# eMMC.net
KiCad netlist of a schematic drawn in Altium Designer
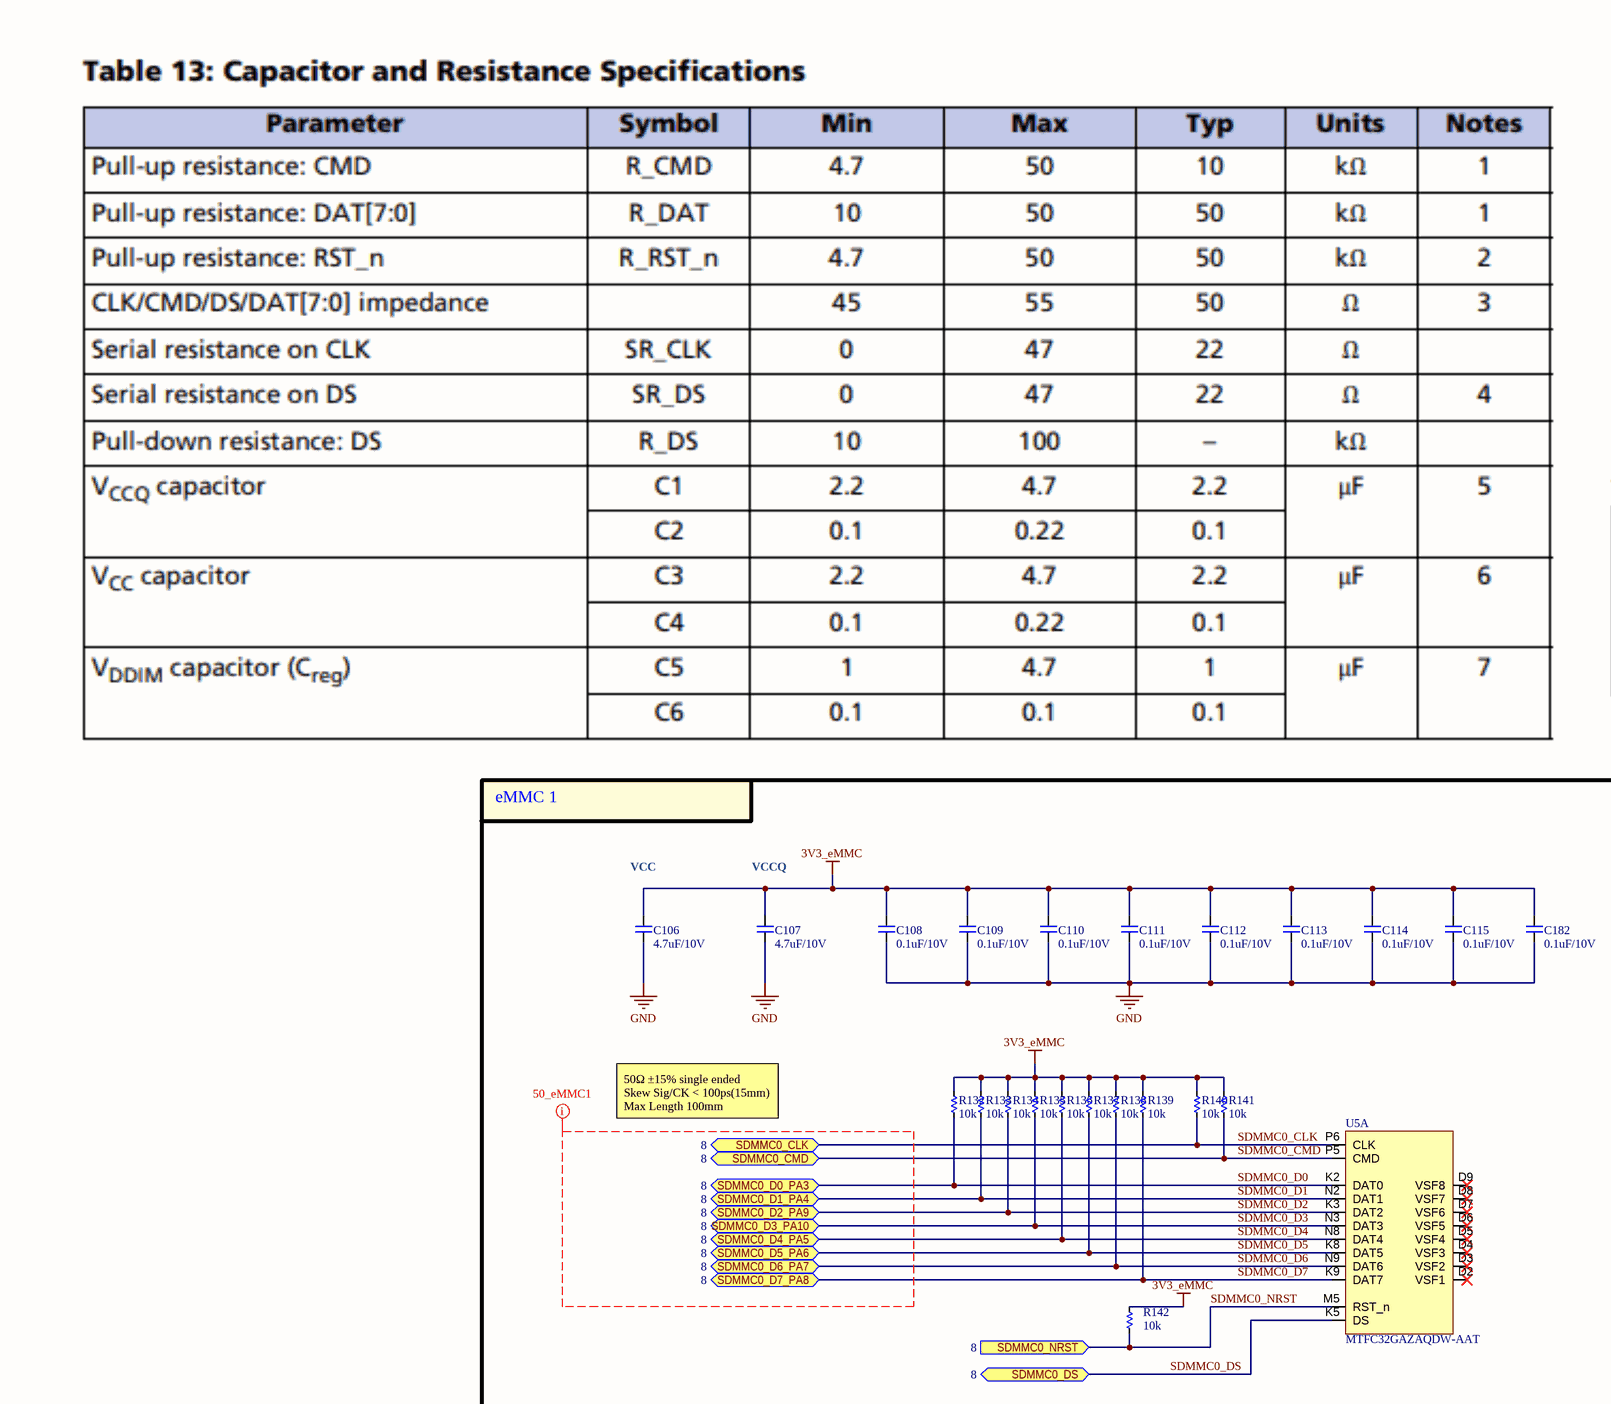
[diagram p0: eMMC.SchDoc, top left]
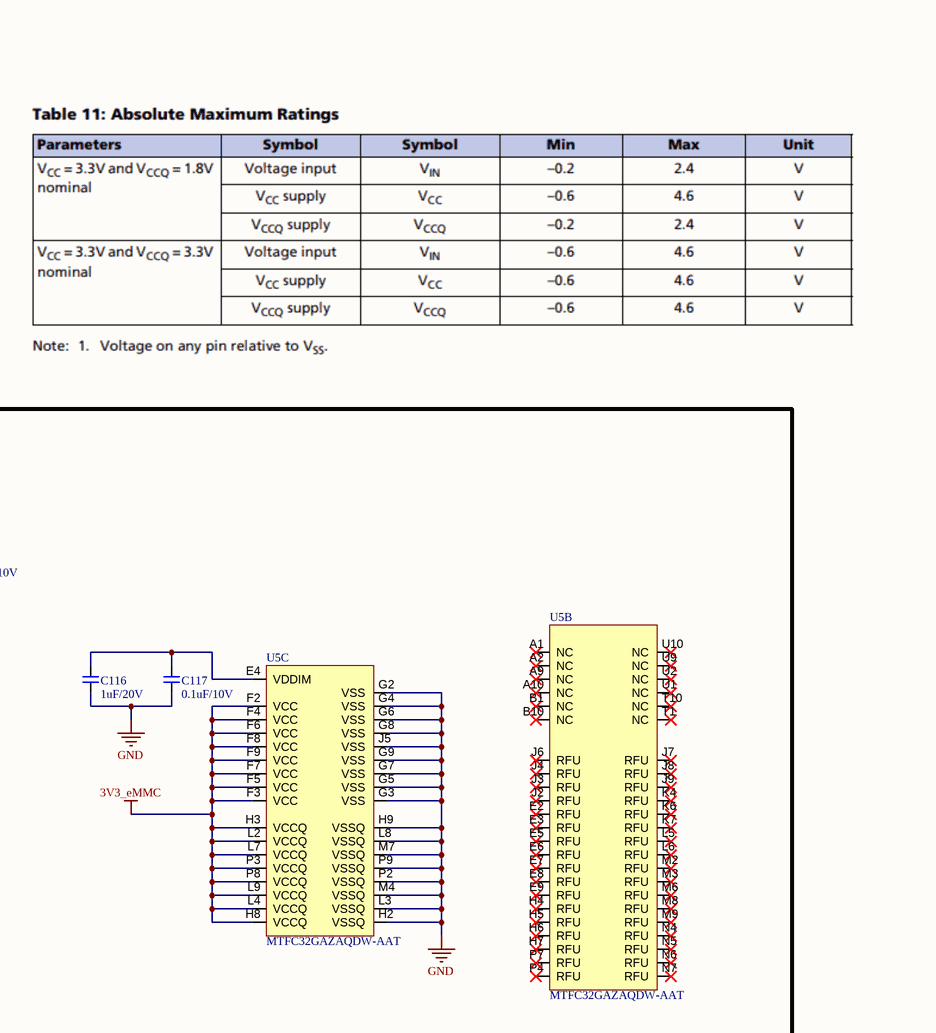
[diagram p1: eMMC.SchDoc, top middle]
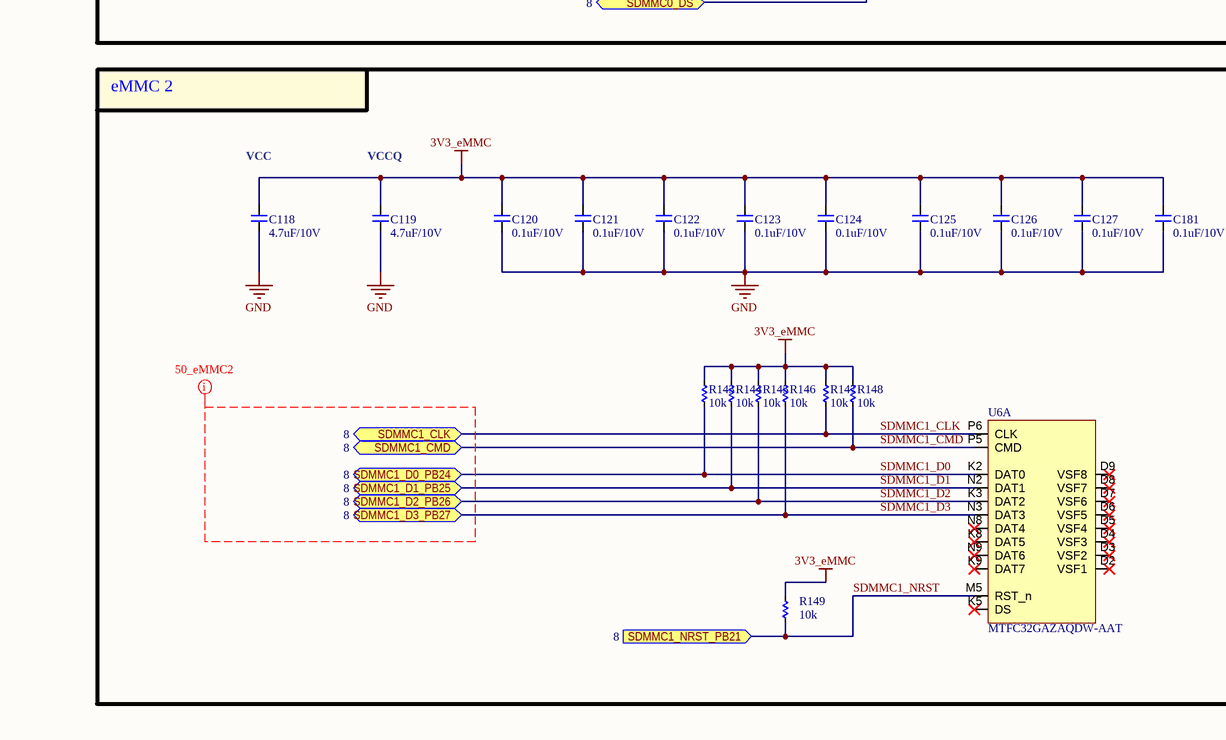
[diagram p2: eMMC.SchDoc, bottom left]
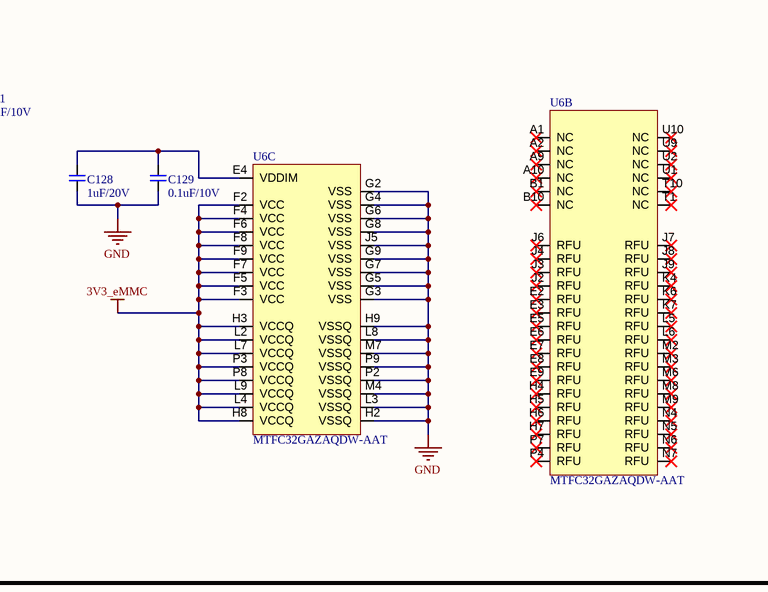
[diagram p3: eMMC.SchDoc, bottom middle]
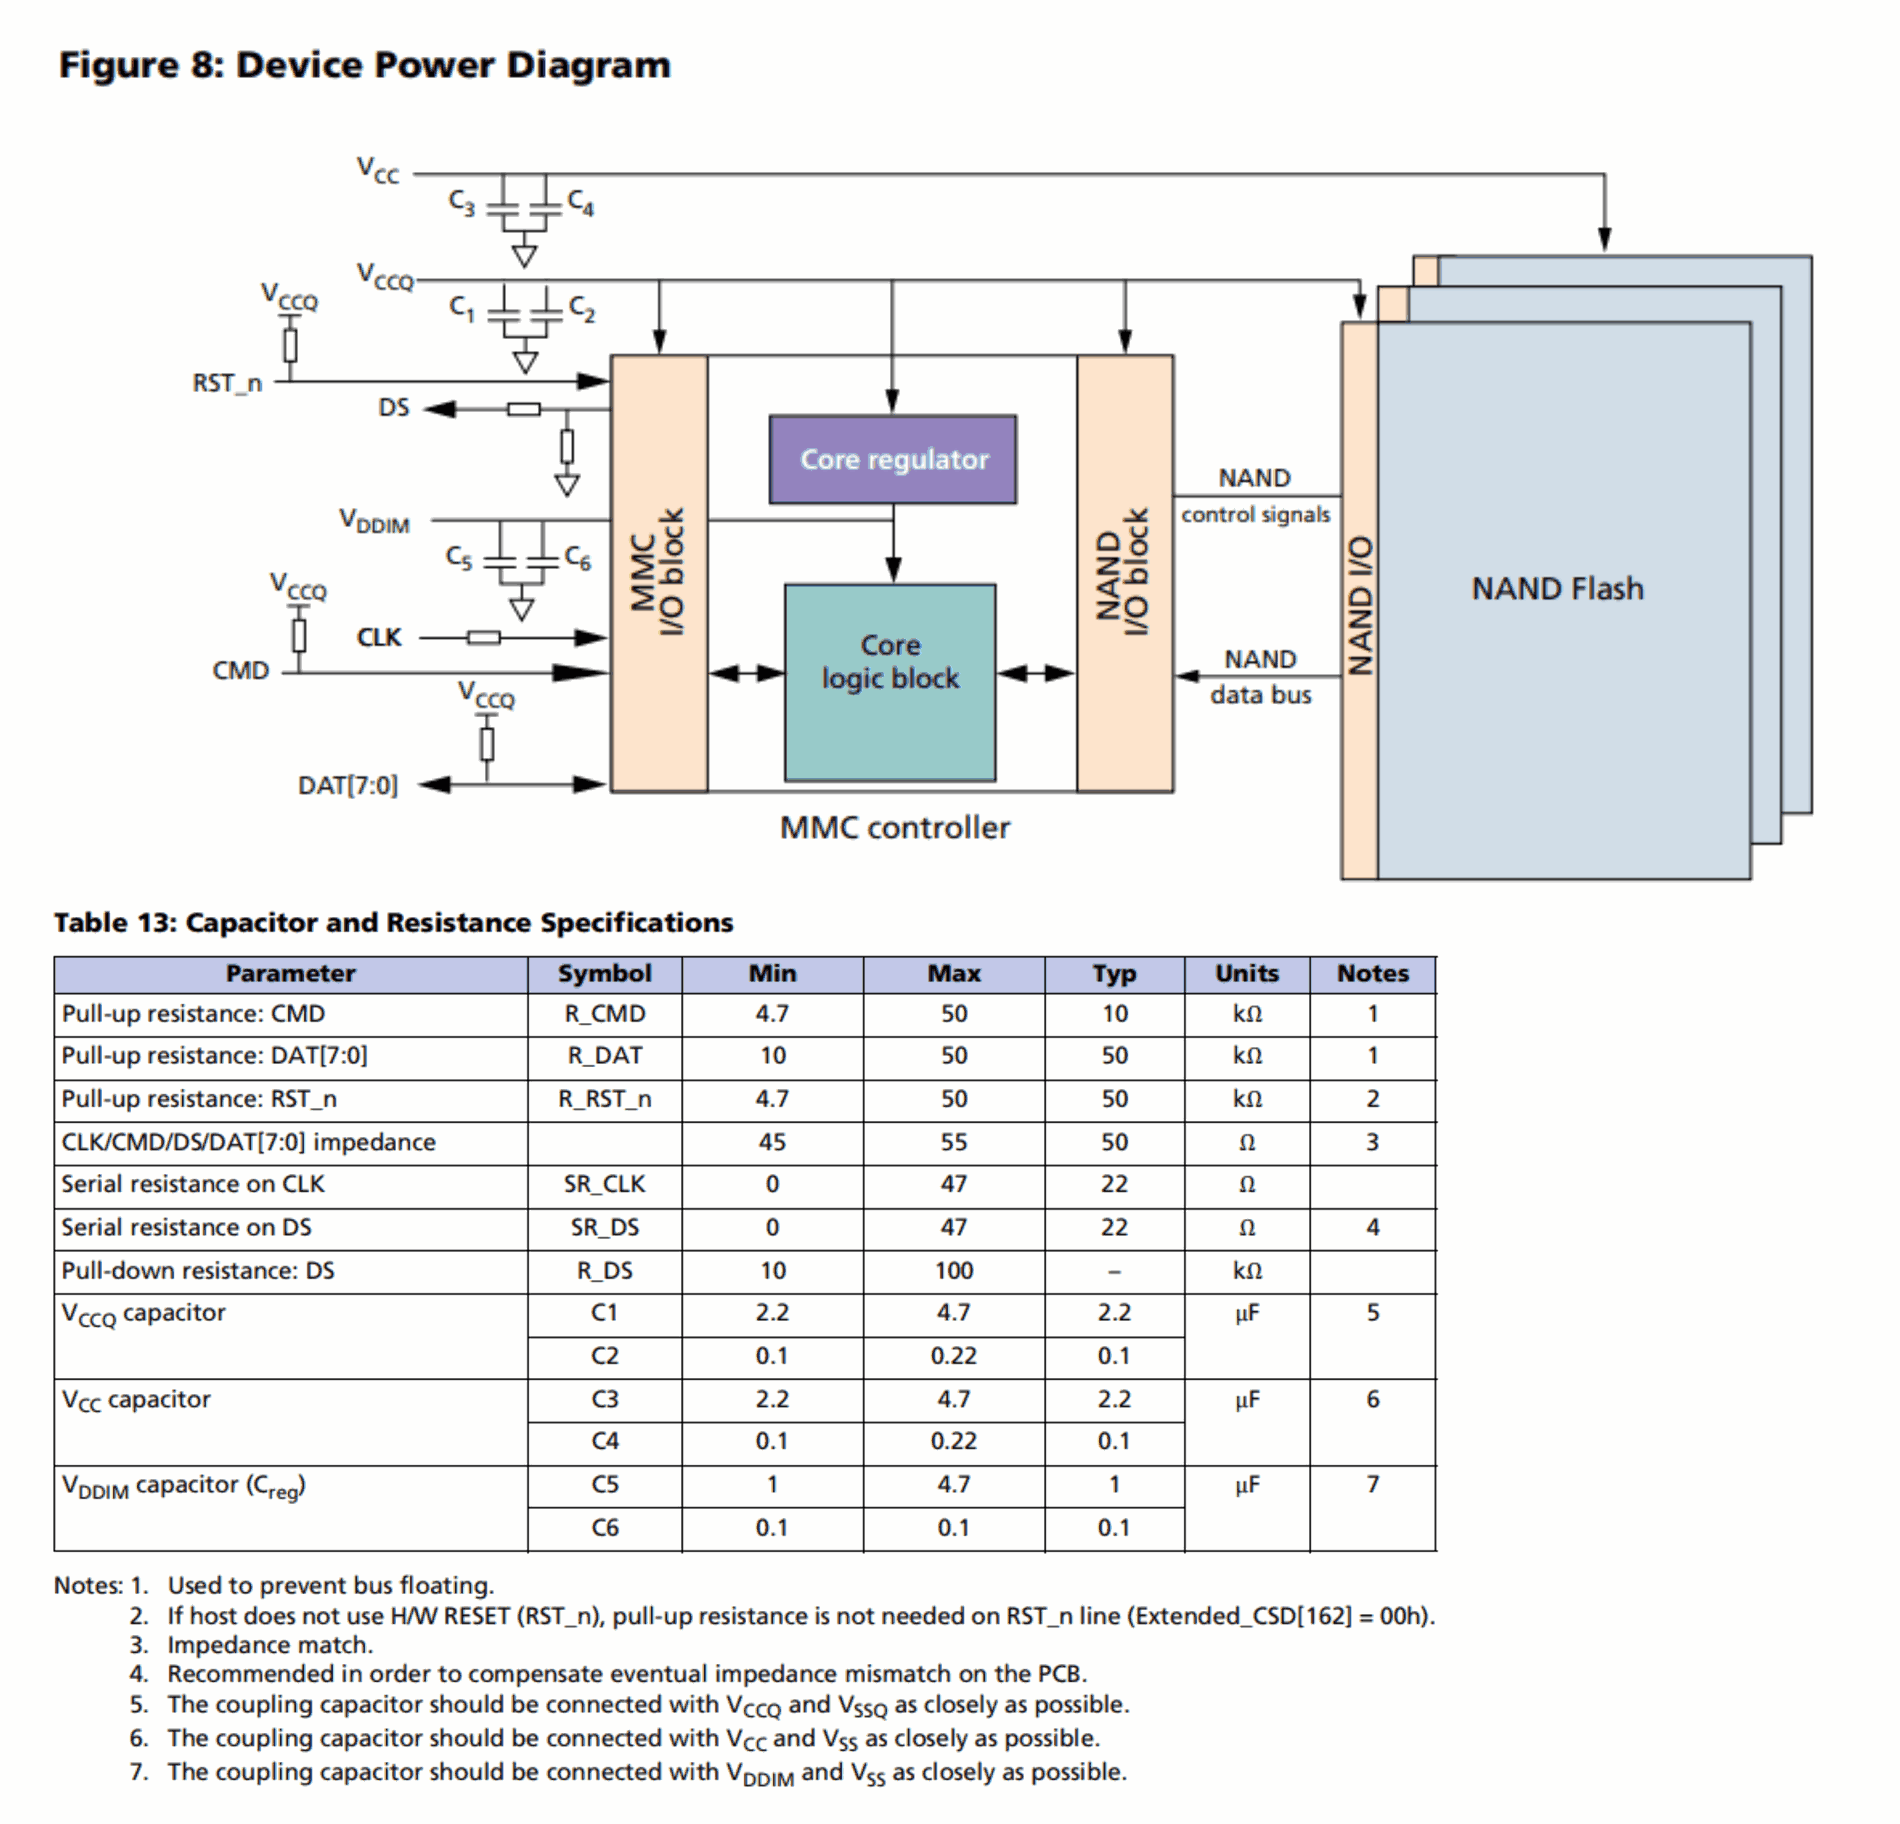
[diagram p4: eMMC.SchDoc, bottom right]

(export (version "E")
  (design (tool "Eeschema 10.0.6"))
  (components
    (comp (ref "C106")
      (value "4.7uF/10V")
      (footprint "CAP_C_1005X50_L")
      (description "CAP CHIP")
      (libsource (lib "IFBschelib") (part "_CAP_C_2"))
    )
    (comp (ref "C107")
      (value "4.7uF/10V")
      (footprint "CAP_C_1005X50_L")
      (description "CAP CHIP")
      (libsource (lib "IFBschelib") (part "_CAP_C_2"))
    )
    (comp (ref "C108")
      (value "0.1uF/10V")
      (footprint "CAP_C_1005X50_L")
      (description "CAP CHIP")
      (libsource (lib "IFBschelib") (part "_CAP_C_2"))
    )
    (comp (ref "C109")
      (value "0.1uF/10V")
      (footprint "CAP_C_1005X50_L")
      (description "CAP CHIP")
      (libsource (lib "IFBschelib") (part "_CAP_C_2"))
    )
    (comp (ref "C110")
      (value "0.1uF/10V")
      (footprint "CAP_C_1005X50_L")
      (description "CAP CHIP")
      (libsource (lib "IFBschelib") (part "_CAP_C_2"))
    )
    (comp (ref "C111")
      (value "0.1uF/10V")
      (footprint "CAP_C_1005X50_L")
      (description "CAP CHIP")
      (libsource (lib "IFBschelib") (part "_CAP_C_2"))
    )
    (comp (ref "C112")
      (value "0.1uF/10V")
      (footprint "CAP_C_1005X50_L")
      (description "CAP CHIP")
      (libsource (lib "IFBschelib") (part "_CAP_C_2"))
    )
    (comp (ref "C113")
      (value "0.1uF/10V")
      (footprint "CAP_C_1005X50_L")
      (description "CAP CHIP")
      (libsource (lib "IFBschelib") (part "_CAP_C_2"))
    )
    (comp (ref "C114")
      (value "0.1uF/10V")
      (footprint "CAP_C_1005X50_L")
      (description "CAP CHIP")
      (libsource (lib "IFBschelib") (part "_CAP_C_2"))
    )
    (comp (ref "C115")
      (value "0.1uF/10V")
      (footprint "CAP_C_1005X50_L")
      (description "CAP CHIP")
      (libsource (lib "IFBschelib") (part "_CAP_C_2"))
    )
    (comp (ref "C116")
      (value "1uF/20V")
      (footprint "CAP_C_1005X50_L")
      (description "CAP CHIP")
      (libsource (lib "IFBschelib") (part "_CAP_C_2"))
    )
    (comp (ref "C117")
      (value "0.1uF/10V")
      (footprint "CAP_C_1005X50_L")
      (description "CAP CHIP")
      (libsource (lib "IFBschelib") (part "_CAP_C_2"))
    )
    (comp (ref "C118")
      (value "4.7uF/10V")
      (footprint "CAP_C_1005X50_L")
      (description "CAP CHIP")
      (libsource (lib "IFBschelib") (part "_CAP_C_2"))
    )
    (comp (ref "C119")
      (value "4.7uF/10V")
      (footprint "CAP_C_1005X50_L")
      (description "CAP CHIP")
      (libsource (lib "IFBschelib") (part "_CAP_C_2"))
    )
    (comp (ref "C120")
      (value "0.1uF/10V")
      (footprint "CAP_C_1005X50_L")
      (description "CAP CHIP")
      (libsource (lib "IFBschelib") (part "_CAP_C_2"))
    )
    (comp (ref "C121")
      (value "0.1uF/10V")
      (footprint "CAP_C_1005X50_L")
      (description "CAP CHIP")
      (libsource (lib "IFBschelib") (part "_CAP_C_2"))
    )
    (comp (ref "C122")
      (value "0.1uF/10V")
      (footprint "CAP_C_1005X50_L")
      (description "CAP CHIP")
      (libsource (lib "IFBschelib") (part "_CAP_C_2"))
    )
    (comp (ref "C123")
      (value "0.1uF/10V")
      (footprint "CAP_C_1005X50_L")
      (description "CAP CHIP")
      (libsource (lib "IFBschelib") (part "_CAP_C_2"))
    )
    (comp (ref "C124")
      (value "0.1uF/10V")
      (footprint "CAP_C_1005X50_L")
      (description "CAP CHIP")
      (libsource (lib "IFBschelib") (part "_CAP_C_2"))
    )
    (comp (ref "C125")
      (value "0.1uF/10V")
      (footprint "CAP_C_1005X50_L")
      (description "CAP CHIP")
      (libsource (lib "IFBschelib") (part "_CAP_C_2"))
    )
    (comp (ref "C126")
      (value "0.1uF/10V")
      (footprint "CAP_C_1005X50_L")
      (description "CAP CHIP")
      (libsource (lib "IFBschelib") (part "_CAP_C_2"))
    )
    (comp (ref "C127")
      (value "0.1uF/10V")
      (footprint "CAP_C_1005X50_L")
      (description "CAP CHIP")
      (libsource (lib "IFBschelib") (part "_CAP_C_2"))
    )
    (comp (ref "C128")
      (value "1uF/20V")
      (footprint "CAP_C_1005X50_L")
      (description "CAP CHIP")
      (libsource (lib "IFBschelib") (part "_CAP_C_2"))
    )
    (comp (ref "C129")
      (value "0.1uF/10V")
      (footprint "CAP_C_1005X50_L")
      (description "CAP CHIP")
      (libsource (lib "IFBschelib") (part "_CAP_C_2"))
    )
    (comp (ref "C181")
      (value "0.1uF/10V")
      (footprint "CAP_C_1005X50_L")
      (description "CAP CHIP")
      (libsource (lib "IFBschelib") (part "_CAP_C_2"))
    )
    (comp (ref "C182")
      (value "0.1uF/10V")
      (footprint "CAP_C_1005X50_L")
      (description "CAP CHIP")
      (libsource (lib "IFBschelib") (part "_CAP_C_2"))
    )
    (comp (ref "R132")
      (value "10k")
      (footprint "RES_C_1005x30_L")
      (description "RES")
      (libsource (lib "IFBschelib") (part "_RES_B_2"))
    )
    (comp (ref "R133")
      (value "10k")
      (footprint "RES_C_1005x30_L")
      (description "RES")
      (libsource (lib "IFBschelib") (part "_RES_B_2"))
    )
    (comp (ref "R134")
      (value "10k")
      (footprint "RES_C_1005x30_L")
      (description "RES")
      (libsource (lib "IFBschelib") (part "_RES_B_2"))
    )
    (comp (ref "R135")
      (value "10k")
      (footprint "RES_C_1005x30_L")
      (description "RES")
      (libsource (lib "IFBschelib") (part "_RES_B_2"))
    )
    (comp (ref "R136")
      (value "10k")
      (footprint "RES_C_1005x30_L")
      (description "RES")
      (libsource (lib "IFBschelib") (part "_RES_B_2"))
    )
    (comp (ref "R137")
      (value "10k")
      (footprint "RES_C_1005x30_L")
      (description "RES")
      (libsource (lib "IFBschelib") (part "_RES_B_2"))
    )
    (comp (ref "R138")
      (value "10k")
      (footprint "RES_C_1005x30_L")
      (description "RES")
      (libsource (lib "IFBschelib") (part "_RES_B_2"))
    )
    (comp (ref "R139")
      (value "10k")
      (footprint "RES_C_1005x30_L")
      (description "RES")
      (libsource (lib "IFBschelib") (part "_RES_B_2"))
    )
    (comp (ref "R140")
      (value "10k")
      (footprint "RES_C_1005x30_L")
      (description "RES")
      (libsource (lib "IFBschelib") (part "_RES_B_2"))
    )
    (comp (ref "R141")
      (value "10k")
      (footprint "RES_C_1005x30_L")
      (description "RES")
      (libsource (lib "IFBschelib") (part "_RES_B_2"))
    )
    (comp (ref "R142")
      (value "10k")
      (footprint "RES_C_1005x30_L")
      (description "RES")
      (libsource (lib "IFBschelib") (part "_RES_B_2"))
    )
    (comp (ref "R143")
      (value "10k")
      (footprint "RES_C_1005x30_L")
      (description "RES")
      (libsource (lib "IFBschelib") (part "_RES_B_2"))
    )
    (comp (ref "R144")
      (value "10k")
      (footprint "RES_C_1005x30_L")
      (description "RES")
      (libsource (lib "IFBschelib") (part "_RES_B_2"))
    )
    (comp (ref "R145")
      (value "10k")
      (footprint "RES_C_1005x30_L")
      (description "RES")
      (libsource (lib "IFBschelib") (part "_RES_B_2"))
    )
    (comp (ref "R146")
      (value "10k")
      (footprint "RES_C_1005x30_L")
      (description "RES")
      (libsource (lib "IFBschelib") (part "_RES_B_2"))
    )
    (comp (ref "R147")
      (value "10k")
      (footprint "RES_C_1005x30_L")
      (description "RES")
      (libsource (lib "IFBschelib") (part "_RES_B_2"))
    )
    (comp (ref "R148")
      (value "10k")
      (footprint "RES_C_1005x30_L")
      (description "RES")
      (libsource (lib "IFBschelib") (part "_RES_B_2"))
    )
    (comp (ref "R149")
      (value "10k")
      (footprint "RES_C_1005x30_L")
      (description "RES")
      (libsource (lib "IFBschelib") (part "_RES_B_2"))
    )
    (comp (ref "U5")
      (value "MTFC32GAZAQDW-AAT")
      (footprint "BGA_100_C_100P_10X17_1400X1800X150")
      (libsource (lib "IFBschelib") (part "MTFC32GAZAQDW-AAT"))
    )
    (comp (ref "U6")
      (value "MTFC32GAZAQDW-AAT")
      (footprint "BGA_100_C_100P_10X17_1400X1800X150")
      (libsource (lib "IFBschelib") (part "MTFC32GAZAQDW-AAT"))
    )
  )
  (nets
    (net (code "1") (name "/SDMMC0_CLK") (class "Default")
      (node (ref "R140") (pin "2") (pinfunction "2_2") (pintype "passive"))
      (node (ref "U5") (pin "P6") (pinfunction "CLK_P6") (pintype "passive"))
    )
    (net (code "2") (name "/SDMMC0_CMD") (class "Default")
      (node (ref "R141") (pin "2") (pinfunction "2_2") (pintype "passive"))
      (node (ref "U5") (pin "P5") (pinfunction "CMD_P5") (pintype "passive"))
    )
    (net (code "3") (name "/SDMMC0_D0") (class "Default")
      (node (ref "R132") (pin "2") (pinfunction "2_2") (pintype "passive"))
      (node (ref "U5") (pin "K2") (pinfunction "DAT0_K2") (pintype "passive"))
    )
    (net (code "4") (name "/SDMMC0_D1") (class "Default")
      (node (ref "R133") (pin "2") (pinfunction "2_2") (pintype "passive"))
      (node (ref "U5") (pin "N2") (pinfunction "DAT1_N2") (pintype "passive"))
    )
    (net (code "5") (name "/SDMMC0_D2") (class "Default")
      (node (ref "R134") (pin "2") (pinfunction "2_2") (pintype "passive"))
      (node (ref "U5") (pin "K3") (pinfunction "DAT2_K3") (pintype "passive"))
    )
    (net (code "6") (name "/SDMMC0_D3") (class "Default")
      (node (ref "R135") (pin "2") (pinfunction "2_2") (pintype "passive"))
      (node (ref "U5") (pin "N3") (pinfunction "DAT3_N3") (pintype "passive"))
    )
    (net (code "7") (name "/SDMMC0_D4") (class "Default")
      (node (ref "R136") (pin "2") (pinfunction "2_2") (pintype "passive"))
      (node (ref "U5") (pin "N8") (pinfunction "DAT4_N8") (pintype "passive"))
    )
    (net (code "8") (name "/SDMMC0_D5") (class "Default")
      (node (ref "R137") (pin "2") (pinfunction "2_2") (pintype "passive"))
      (node (ref "U5") (pin "K8") (pinfunction "DAT5_K8") (pintype "passive"))
    )
    (net (code "9") (name "/SDMMC0_D6") (class "Default")
      (node (ref "R138") (pin "2") (pinfunction "2_2") (pintype "passive"))
      (node (ref "U5") (pin "N9") (pinfunction "DAT6_N9") (pintype "passive"))
    )
    (net (code "10") (name "/SDMMC0_D7") (class "Default")
      (node (ref "R139") (pin "2") (pinfunction "2_2") (pintype "passive"))
      (node (ref "U5") (pin "K9") (pinfunction "DAT7_K9") (pintype "passive"))
    )
    (net (code "11") (name "/SDMMC0_DS") (class "Default")
      (node (ref "U5") (pin "K5") (pinfunction "DS_K5") (pintype "passive"))
    )
    (net (code "12") (name "/SDMMC0_NRST") (class "Default")
      (node (ref "R142") (pin "2") (pinfunction "2_2") (pintype "passive"))
      (node (ref "U5") (pin "M5") (pinfunction "RST_n_M5") (pintype "passive"))
    )
    (net (code "13") (name "/SDMMC1_CLK") (class "Default")
      (node (ref "R147") (pin "2") (pinfunction "2_2") (pintype "passive"))
      (node (ref "U6") (pin "P6") (pinfunction "CLK_P6") (pintype "passive"))
    )
    (net (code "14") (name "/SDMMC1_CMD") (class "Default")
      (node (ref "R148") (pin "2") (pinfunction "2_2") (pintype "passive"))
      (node (ref "U6") (pin "P5") (pinfunction "CMD_P5") (pintype "passive"))
    )
    (net (code "15") (name "/SDMMC1_D0") (class "Default")
      (node (ref "R143") (pin "2") (pinfunction "2_2") (pintype "passive"))
      (node (ref "U6") (pin "K2") (pinfunction "DAT0_K2") (pintype "passive"))
    )
    (net (code "16") (name "/SDMMC1_D1") (class "Default")
      (node (ref "R144") (pin "2") (pinfunction "2_2") (pintype "passive"))
      (node (ref "U6") (pin "N2") (pinfunction "DAT1_N2") (pintype "passive"))
    )
    (net (code "17") (name "/SDMMC1_D2") (class "Default")
      (node (ref "R145") (pin "2") (pinfunction "2_2") (pintype "passive"))
      (node (ref "U6") (pin "K3") (pinfunction "DAT2_K3") (pintype "passive"))
    )
    (net (code "18") (name "/SDMMC1_D3") (class "Default")
      (node (ref "R146") (pin "2") (pinfunction "2_2") (pintype "passive"))
      (node (ref "U6") (pin "N3") (pinfunction "DAT3_N3") (pintype "passive"))
    )
    (net (code "19") (name "/SDMMC1_NRST") (class "Default")
      (node (ref "R149") (pin "2") (pinfunction "2_2") (pintype "passive"))
      (node (ref "U6") (pin "M5") (pinfunction "RST_n_M5") (pintype "passive"))
    )
    (net (code "20") (name "3V3_eMMC") (class "Default")
      (node (ref "C106") (pin "2") (pinfunction "2_2") (pintype "passive"))
      (node (ref "C107") (pin "2") (pinfunction "2_2") (pintype "passive"))
      (node (ref "C108") (pin "2") (pinfunction "2_2") (pintype "passive"))
      (node (ref "C109") (pin "2") (pinfunction "2_2") (pintype "passive"))
      (node (ref "C110") (pin "2") (pinfunction "2_2") (pintype "passive"))
      (node (ref "C111") (pin "2") (pinfunction "2_2") (pintype "passive"))
      (node (ref "C112") (pin "2") (pinfunction "2_2") (pintype "passive"))
      (node (ref "C113") (pin "2") (pinfunction "2_2") (pintype "passive"))
      (node (ref "C114") (pin "2") (pinfunction "2_2") (pintype "passive"))
      (node (ref "C115") (pin "2") (pinfunction "2_2") (pintype "passive"))
      (node (ref "C118") (pin "2") (pinfunction "2_2") (pintype "passive"))
      (node (ref "C119") (pin "2") (pinfunction "2_2") (pintype "passive"))
      (node (ref "C120") (pin "2") (pinfunction "2_2") (pintype "passive"))
      (node (ref "C121") (pin "2") (pinfunction "2_2") (pintype "passive"))
      (node (ref "C122") (pin "2") (pinfunction "2_2") (pintype "passive"))
      (node (ref "C123") (pin "2") (pinfunction "2_2") (pintype "passive"))
      (node (ref "C124") (pin "2") (pinfunction "2_2") (pintype "passive"))
      (node (ref "C125") (pin "2") (pinfunction "2_2") (pintype "passive"))
      (node (ref "C126") (pin "2") (pinfunction "2_2") (pintype "passive"))
      (node (ref "C127") (pin "2") (pinfunction "2_2") (pintype "passive"))
      (node (ref "C181") (pin "2") (pinfunction "2_2") (pintype "passive"))
      (node (ref "C182") (pin "2") (pinfunction "2_2") (pintype "passive"))
      (node (ref "R132") (pin "1") (pinfunction "1_1") (pintype "passive"))
      (node (ref "R133") (pin "1") (pinfunction "1_1") (pintype "passive"))
      (node (ref "R134") (pin "1") (pinfunction "1_1") (pintype "passive"))
      (node (ref "R135") (pin "1") (pinfunction "1_1") (pintype "passive"))
      (node (ref "R136") (pin "1") (pinfunction "1_1") (pintype "passive"))
      (node (ref "R137") (pin "1") (pinfunction "1_1") (pintype "passive"))
      (node (ref "R138") (pin "1") (pinfunction "1_1") (pintype "passive"))
      (node (ref "R139") (pin "1") (pinfunction "1_1") (pintype "passive"))
      (node (ref "R140") (pin "1") (pinfunction "1_1") (pintype "passive"))
      (node (ref "R141") (pin "1") (pinfunction "1_1") (pintype "passive"))
      (node (ref "R142") (pin "1") (pinfunction "1_1") (pintype "passive"))
      (node (ref "R143") (pin "1") (pinfunction "1_1") (pintype "passive"))
      (node (ref "R144") (pin "1") (pinfunction "1_1") (pintype "passive"))
      (node (ref "R145") (pin "1") (pinfunction "1_1") (pintype "passive"))
      (node (ref "R146") (pin "1") (pinfunction "1_1") (pintype "passive"))
      (node (ref "R147") (pin "1") (pinfunction "1_1") (pintype "passive"))
      (node (ref "R148") (pin "1") (pinfunction "1_1") (pintype "passive"))
      (node (ref "R149") (pin "1") (pinfunction "1_1") (pintype "passive"))
      (node (ref "U5") (pin "F2") (pinfunction "VCC_F2") (pintype "passive"))
      (node (ref "U5") (pin "F3") (pinfunction "VCC_F3") (pintype "passive"))
      (node (ref "U5") (pin "F4") (pinfunction "VCC_F4") (pintype "passive"))
      (node (ref "U5") (pin "F5") (pinfunction "VCC_F5") (pintype "passive"))
      (node (ref "U5") (pin "F6") (pinfunction "VCC_F6") (pintype "passive"))
      (node (ref "U5") (pin "F7") (pinfunction "VCC_F7") (pintype "passive"))
      (node (ref "U5") (pin "F8") (pinfunction "VCC_F8") (pintype "passive"))
      (node (ref "U5") (pin "F9") (pinfunction "VCC_F9") (pintype "passive"))
      (node (ref "U5") (pin "H3") (pinfunction "VCCQ_H3") (pintype "passive"))
      (node (ref "U5") (pin "H8") (pinfunction "VCCQ_H8") (pintype "passive"))
      (node (ref "U5") (pin "L2") (pinfunction "VCCQ_L2") (pintype "passive"))
      (node (ref "U5") (pin "L4") (pinfunction "VCCQ_L4") (pintype "passive"))
      (node (ref "U5") (pin "L7") (pinfunction "VCCQ_L7") (pintype "passive"))
      (node (ref "U5") (pin "L9") (pinfunction "VCCQ_L9") (pintype "passive"))
      (node (ref "U5") (pin "P3") (pinfunction "VCCQ_P3") (pintype "passive"))
      (node (ref "U5") (pin "P8") (pinfunction "VCCQ_P8") (pintype "passive"))
      (node (ref "U6") (pin "F2") (pinfunction "VCC_F2") (pintype "passive"))
      (node (ref "U6") (pin "F3") (pinfunction "VCC_F3") (pintype "passive"))
      (node (ref "U6") (pin "F4") (pinfunction "VCC_F4") (pintype "passive"))
      (node (ref "U6") (pin "F5") (pinfunction "VCC_F5") (pintype "passive"))
      (node (ref "U6") (pin "F6") (pinfunction "VCC_F6") (pintype "passive"))
      (node (ref "U6") (pin "F7") (pinfunction "VCC_F7") (pintype "passive"))
      (node (ref "U6") (pin "F8") (pinfunction "VCC_F8") (pintype "passive"))
      (node (ref "U6") (pin "F9") (pinfunction "VCC_F9") (pintype "passive"))
      (node (ref "U6") (pin "H3") (pinfunction "VCCQ_H3") (pintype "passive"))
      (node (ref "U6") (pin "H8") (pinfunction "VCCQ_H8") (pintype "passive"))
      (node (ref "U6") (pin "L2") (pinfunction "VCCQ_L2") (pintype "passive"))
      (node (ref "U6") (pin "L4") (pinfunction "VCCQ_L4") (pintype "passive"))
      (node (ref "U6") (pin "L7") (pinfunction "VCCQ_L7") (pintype "passive"))
      (node (ref "U6") (pin "L9") (pinfunction "VCCQ_L9") (pintype "passive"))
      (node (ref "U6") (pin "P3") (pinfunction "VCCQ_P3") (pintype "passive"))
      (node (ref "U6") (pin "P8") (pinfunction "VCCQ_P8") (pintype "passive"))
    )
    (net (code "21") (name "GND") (class "Default")
      (node (ref "C106") (pin "1") (pinfunction "1_1") (pintype "passive"))
      (node (ref "C107") (pin "1") (pinfunction "1_1") (pintype "passive"))
      (node (ref "C108") (pin "1") (pinfunction "1_1") (pintype "passive"))
      (node (ref "C109") (pin "1") (pinfunction "1_1") (pintype "passive"))
      (node (ref "C110") (pin "1") (pinfunction "1_1") (pintype "passive"))
      (node (ref "C111") (pin "1") (pinfunction "1_1") (pintype "passive"))
      (node (ref "C112") (pin "1") (pinfunction "1_1") (pintype "passive"))
      (node (ref "C113") (pin "1") (pinfunction "1_1") (pintype "passive"))
      (node (ref "C114") (pin "1") (pinfunction "1_1") (pintype "passive"))
      (node (ref "C115") (pin "1") (pinfunction "1_1") (pintype "passive"))
      (node (ref "C116") (pin "1") (pinfunction "1_1") (pintype "passive"))
      (node (ref "C117") (pin "1") (pinfunction "1_1") (pintype "passive"))
      (node (ref "C118") (pin "1") (pinfunction "1_1") (pintype "passive"))
      (node (ref "C119") (pin "1") (pinfunction "1_1") (pintype "passive"))
      (node (ref "C120") (pin "1") (pinfunction "1_1") (pintype "passive"))
      (node (ref "C121") (pin "1") (pinfunction "1_1") (pintype "passive"))
      (node (ref "C122") (pin "1") (pinfunction "1_1") (pintype "passive"))
      (node (ref "C123") (pin "1") (pinfunction "1_1") (pintype "passive"))
      (node (ref "C124") (pin "1") (pinfunction "1_1") (pintype "passive"))
      (node (ref "C125") (pin "1") (pinfunction "1_1") (pintype "passive"))
      (node (ref "C126") (pin "1") (pinfunction "1_1") (pintype "passive"))
      (node (ref "C127") (pin "1") (pinfunction "1_1") (pintype "passive"))
      (node (ref "C128") (pin "1") (pinfunction "1_1") (pintype "passive"))
      (node (ref "C129") (pin "1") (pinfunction "1_1") (pintype "passive"))
      (node (ref "C181") (pin "1") (pinfunction "1_1") (pintype "passive"))
      (node (ref "C182") (pin "1") (pinfunction "1_1") (pintype "passive"))
      (node (ref "U5") (pin "G2") (pinfunction "VSS_G2") (pintype "passive"))
      (node (ref "U5") (pin "G3") (pinfunction "VSS_G3") (pintype "passive"))
      (node (ref "U5") (pin "G4") (pinfunction "VSS_G4") (pintype "passive"))
      (node (ref "U5") (pin "G5") (pinfunction "VSS_G5") (pintype "passive"))
      (node (ref "U5") (pin "G6") (pinfunction "VSS_G6") (pintype "passive"))
      (node (ref "U5") (pin "G7") (pinfunction "VSS_G7") (pintype "passive"))
      (node (ref "U5") (pin "G8") (pinfunction "VSS_G8") (pintype "passive"))
      (node (ref "U5") (pin "G9") (pinfunction "VSS_G9") (pintype "passive"))
      (node (ref "U5") (pin "H2") (pinfunction "VSSQ_H2") (pintype "passive"))
      (node (ref "U5") (pin "H9") (pinfunction "VSSQ_H9") (pintype "passive"))
      (node (ref "U5") (pin "J5") (pinfunction "VSS_J5") (pintype "passive"))
      (node (ref "U5") (pin "L3") (pinfunction "VSSQ_L3") (pintype "passive"))
      (node (ref "U5") (pin "L8") (pinfunction "VSSQ_L8") (pintype "passive"))
      (node (ref "U5") (pin "M4") (pinfunction "VSSQ_M4") (pintype "passive"))
      (node (ref "U5") (pin "M7") (pinfunction "VSSQ_M7") (pintype "passive"))
      (node (ref "U5") (pin "P2") (pinfunction "VSSQ_P2") (pintype "passive"))
      (node (ref "U5") (pin "P9") (pinfunction "VSSQ_P9") (pintype "passive"))
      (node (ref "U6") (pin "G2") (pinfunction "VSS_G2") (pintype "passive"))
      (node (ref "U6") (pin "G3") (pinfunction "VSS_G3") (pintype "passive"))
      (node (ref "U6") (pin "G4") (pinfunction "VSS_G4") (pintype "passive"))
      (node (ref "U6") (pin "G5") (pinfunction "VSS_G5") (pintype "passive"))
      (node (ref "U6") (pin "G6") (pinfunction "VSS_G6") (pintype "passive"))
      (node (ref "U6") (pin "G7") (pinfunction "VSS_G7") (pintype "passive"))
      (node (ref "U6") (pin "G8") (pinfunction "VSS_G8") (pintype "passive"))
      (node (ref "U6") (pin "G9") (pinfunction "VSS_G9") (pintype "passive"))
      (node (ref "U6") (pin "H2") (pinfunction "VSSQ_H2") (pintype "passive"))
      (node (ref "U6") (pin "H9") (pinfunction "VSSQ_H9") (pintype "passive"))
      (node (ref "U6") (pin "J5") (pinfunction "VSS_J5") (pintype "passive"))
      (node (ref "U6") (pin "L3") (pinfunction "VSSQ_L3") (pintype "passive"))
      (node (ref "U6") (pin "L8") (pinfunction "VSSQ_L8") (pintype "passive"))
      (node (ref "U6") (pin "M4") (pinfunction "VSSQ_M4") (pintype "passive"))
      (node (ref "U6") (pin "M7") (pinfunction "VSSQ_M7") (pintype "passive"))
      (node (ref "U6") (pin "P2") (pinfunction "VSSQ_P2") (pintype "passive"))
      (node (ref "U6") (pin "P9") (pinfunction "VSSQ_P9") (pintype "passive"))
    )
    (net (code "22") (name "Net-(U5C-VDDIM)") (class "Default")
      (node (ref "C116") (pin "2") (pinfunction "2_2") (pintype "passive"))
      (node (ref "C117") (pin "2") (pinfunction "2_2") (pintype "passive"))
      (node (ref "U5") (pin "E4") (pinfunction "VDDIM_E4") (pintype "passive"))
    )
    (net (code "23") (name "Net-(U6C-VDDIM)") (class "Default")
      (node (ref "C128") (pin "2") (pinfunction "2_2") (pintype "passive"))
      (node (ref "C129") (pin "2") (pinfunction "2_2") (pintype "passive"))
      (node (ref "U6") (pin "E4") (pinfunction "VDDIM_E4") (pintype "passive"))
    )
    (net (code "24") (name "unconnected-(U5A-VSF1-PadD2)") (class "Default")
      (node (ref "U5") (pin "D2") (pinfunction "VSF1_D2") (pintype "passive+no_connect"))
    )
    (net (code "25") (name "unconnected-(U5A-VSF2-PadD3)") (class "Default")
      (node (ref "U5") (pin "D3") (pinfunction "VSF2_D3") (pintype "passive+no_connect"))
    )
    (net (code "26") (name "unconnected-(U5A-VSF3-PadD4)") (class "Default")
      (node (ref "U5") (pin "D4") (pinfunction "VSF3_D4") (pintype "passive+no_connect"))
    )
    (net (code "27") (name "unconnected-(U5A-VSF4-PadD5)") (class "Default")
      (node (ref "U5") (pin "D5") (pinfunction "VSF4_D5") (pintype "passive+no_connect"))
    )
    (net (code "28") (name "unconnected-(U5A-VSF5-PadD6)") (class "Default")
      (node (ref "U5") (pin "D6") (pinfunction "VSF5_D6") (pintype "passive+no_connect"))
    )
    (net (code "29") (name "unconnected-(U5A-VSF6-PadD7)") (class "Default")
      (node (ref "U5") (pin "D7") (pinfunction "VSF6_D7") (pintype "passive+no_connect"))
    )
    (net (code "30") (name "unconnected-(U5A-VSF7-PadD8)") (class "Default")
      (node (ref "U5") (pin "D8") (pinfunction "VSF7_D8") (pintype "passive+no_connect"))
    )
    (net (code "31") (name "unconnected-(U5A-VSF8-PadD9)") (class "Default")
      (node (ref "U5") (pin "D9") (pinfunction "VSF8_D9") (pintype "passive+no_connect"))
    )
    (net (code "32") (name "unconnected-(U5B-NC-PadA1)") (class "Default")
      (node (ref "U5") (pin "A1") (pinfunction "NC_A1") (pintype "passive+no_connect"))
    )
    (net (code "33") (name "unconnected-(U5B-NC-PadA2)") (class "Default")
      (node (ref "U5") (pin "A2") (pinfunction "NC_A2") (pintype "passive+no_connect"))
    )
    (net (code "34") (name "unconnected-(U5B-NC-PadA9)") (class "Default")
      (node (ref "U5") (pin "A9") (pinfunction "NC_A9") (pintype "passive+no_connect"))
    )
    (net (code "35") (name "unconnected-(U5B-NC-PadA10)") (class "Default")
      (node (ref "U5") (pin "A10") (pinfunction "NC_A10") (pintype "passive+no_connect"))
    )
    (net (code "36") (name "unconnected-(U5B-NC-PadB1)") (class "Default")
      (node (ref "U5") (pin "B1") (pinfunction "NC_B1") (pintype "passive+no_connect"))
    )
    (net (code "37") (name "unconnected-(U5B-NC-PadB10)") (class "Default")
      (node (ref "U5") (pin "B10") (pinfunction "NC_B10") (pintype "passive+no_connect"))
    )
    (net (code "38") (name "unconnected-(U5B-NC-PadT1)") (class "Default")
      (node (ref "U5") (pin "T1") (pinfunction "NC_T1") (pintype "passive+no_connect"))
    )
    (net (code "39") (name "unconnected-(U5B-NC-PadT10)") (class "Default")
      (node (ref "U5") (pin "T10") (pinfunction "NC_T10") (pintype "passive+no_connect"))
    )
    (net (code "40") (name "unconnected-(U5B-NC-PadU1)") (class "Default")
      (node (ref "U5") (pin "U1") (pinfunction "NC_U1") (pintype "passive+no_connect"))
    )
    (net (code "41") (name "unconnected-(U5B-NC-PadU2)") (class "Default")
      (node (ref "U5") (pin "U2") (pinfunction "NC_U2") (pintype "passive+no_connect"))
    )
    (net (code "42") (name "unconnected-(U5B-NC-PadU9)") (class "Default")
      (node (ref "U5") (pin "U9") (pinfunction "NC_U9") (pintype "passive+no_connect"))
    )
    (net (code "43") (name "unconnected-(U5B-NC-PadU10)") (class "Default")
      (node (ref "U5") (pin "U10") (pinfunction "NC_U10") (pintype "passive+no_connect"))
    )
    (net (code "44") (name "unconnected-(U5B-RFU-PadE2)") (class "Default")
      (node (ref "U5") (pin "E2") (pinfunction "RFU_E2") (pintype "passive+no_connect"))
    )
    (net (code "45") (name "unconnected-(U5B-RFU-PadE3)") (class "Default")
      (node (ref "U5") (pin "E3") (pinfunction "RFU_E3") (pintype "passive+no_connect"))
    )
    (net (code "46") (name "unconnected-(U5B-RFU-PadE5)") (class "Default")
      (node (ref "U5") (pin "E5") (pinfunction "RFU_E5") (pintype "passive+no_connect"))
    )
    (net (code "47") (name "unconnected-(U5B-RFU-PadE6)") (class "Default")
      (node (ref "U5") (pin "E6") (pinfunction "RFU_E6") (pintype "passive+no_connect"))
    )
    (net (code "48") (name "unconnected-(U5B-RFU-PadE7)") (class "Default")
      (node (ref "U5") (pin "E7") (pinfunction "RFU_E7") (pintype "passive+no_connect"))
    )
    (net (code "49") (name "unconnected-(U5B-RFU-PadE8)") (class "Default")
      (node (ref "U5") (pin "E8") (pinfunction "RFU_E8") (pintype "passive+no_connect"))
    )
    (net (code "50") (name "unconnected-(U5B-RFU-PadE9)") (class "Default")
      (node (ref "U5") (pin "E9") (pinfunction "RFU_E9") (pintype "passive+no_connect"))
    )
    (net (code "51") (name "unconnected-(U5B-RFU-PadH4)") (class "Default")
      (node (ref "U5") (pin "H4") (pinfunction "RFU_H4") (pintype "passive+no_connect"))
    )
    (net (code "52") (name "unconnected-(U5B-RFU-PadH5)") (class "Default")
      (node (ref "U5") (pin "H5") (pinfunction "RFU_H5") (pintype "passive+no_connect"))
    )
    (net (code "53") (name "unconnected-(U5B-RFU-PadH6)") (class "Default")
      (node (ref "U5") (pin "H6") (pinfunction "RFU_H6") (pintype "passive+no_connect"))
    )
    (net (code "54") (name "unconnected-(U5B-RFU-PadH7)") (class "Default")
      (node (ref "U5") (pin "H7") (pinfunction "RFU_H7") (pintype "passive+no_connect"))
    )
    (net (code "55") (name "unconnected-(U5B-RFU-PadJ2)") (class "Default")
      (node (ref "U5") (pin "J2") (pinfunction "RFU_J2") (pintype "passive+no_connect"))
    )
    (net (code "56") (name "unconnected-(U5B-RFU-PadJ3)") (class "Default")
      (node (ref "U5") (pin "J3") (pinfunction "RFU_J3") (pintype "passive+no_connect"))
    )
    (net (code "57") (name "unconnected-(U5B-RFU-PadJ4)") (class "Default")
      (node (ref "U5") (pin "J4") (pinfunction "RFU_J4") (pintype "passive+no_connect"))
    )
    (net (code "58") (name "unconnected-(U5B-RFU-PadJ6)") (class "Default")
      (node (ref "U5") (pin "J6") (pinfunction "RFU_J6") (pintype "passive+no_connect"))
    )
    (net (code "59") (name "unconnected-(U5B-RFU-PadJ7)") (class "Default")
      (node (ref "U5") (pin "J7") (pinfunction "RFU_J7") (pintype "passive+no_connect"))
    )
    (net (code "60") (name "unconnected-(U5B-RFU-PadJ8)") (class "Default")
      (node (ref "U5") (pin "J8") (pinfunction "RFU_J8") (pintype "passive+no_connect"))
    )
    (net (code "61") (name "unconnected-(U5B-RFU-PadJ9)") (class "Default")
      (node (ref "U5") (pin "J9") (pinfunction "RFU_J9") (pintype "passive+no_connect"))
    )
    (net (code "62") (name "unconnected-(U5B-RFU-PadK4)") (class "Default")
      (node (ref "U5") (pin "K4") (pinfunction "RFU_K4") (pintype "passive+no_connect"))
    )
    (net (code "63") (name "unconnected-(U5B-RFU-PadK6)") (class "Default")
      (node (ref "U5") (pin "K6") (pinfunction "RFU_K6") (pintype "passive+no_connect"))
    )
    (net (code "64") (name "unconnected-(U5B-RFU-PadK7)") (class "Default")
      (node (ref "U5") (pin "K7") (pinfunction "RFU_K7") (pintype "passive+no_connect"))
    )
    (net (code "65") (name "unconnected-(U5B-RFU-PadL5)") (class "Default")
      (node (ref "U5") (pin "L5") (pinfunction "RFU_L5") (pintype "passive+no_connect"))
    )
    (net (code "66") (name "unconnected-(U5B-RFU-PadL6)") (class "Default")
      (node (ref "U5") (pin "L6") (pinfunction "RFU_L6") (pintype "passive+no_connect"))
    )
    (net (code "67") (name "unconnected-(U5B-RFU-PadM2)") (class "Default")
      (node (ref "U5") (pin "M2") (pinfunction "RFU_M2") (pintype "passive+no_connect"))
    )
    (net (code "68") (name "unconnected-(U5B-RFU-PadM3)") (class "Default")
      (node (ref "U5") (pin "M3") (pinfunction "RFU_M3") (pintype "passive+no_connect"))
    )
    (net (code "69") (name "unconnected-(U5B-RFU-PadM6)") (class "Default")
      (node (ref "U5") (pin "M6") (pinfunction "RFU_M6") (pintype "passive+no_connect"))
    )
    (net (code "70") (name "unconnected-(U5B-RFU-PadM8)") (class "Default")
      (node (ref "U5") (pin "M8") (pinfunction "RFU_M8") (pintype "passive+no_connect"))
    )
    (net (code "71") (name "unconnected-(U5B-RFU-PadM9)") (class "Default")
      (node (ref "U5") (pin "M9") (pinfunction "RFU_M9") (pintype "passive+no_connect"))
    )
    (net (code "72") (name "unconnected-(U5B-RFU-PadN4)") (class "Default")
      (node (ref "U5") (pin "N4") (pinfunction "RFU_N4") (pintype "passive+no_connect"))
    )
    (net (code "73") (name "unconnected-(U5B-RFU-PadN5)") (class "Default")
      (node (ref "U5") (pin "N5") (pinfunction "RFU_N5") (pintype "passive+no_connect"))
    )
    (net (code "74") (name "unconnected-(U5B-RFU-PadN6)") (class "Default")
      (node (ref "U5") (pin "N6") (pinfunction "RFU_N6") (pintype "passive+no_connect"))
    )
    (net (code "75") (name "unconnected-(U5B-RFU-PadN7)") (class "Default")
      (node (ref "U5") (pin "N7") (pinfunction "RFU_N7") (pintype "passive+no_connect"))
    )
    (net (code "76") (name "unconnected-(U5B-RFU-PadP4)") (class "Default")
      (node (ref "U5") (pin "P4") (pinfunction "RFU_P4") (pintype "passive+no_connect"))
    )
    (net (code "77") (name "unconnected-(U5B-RFU-PadP7)") (class "Default")
      (node (ref "U5") (pin "P7") (pinfunction "RFU_P7") (pintype "passive+no_connect"))
    )
    (net (code "78") (name "unconnected-(U6A-DAT4-PadN8)") (class "Default")
      (node (ref "U6") (pin "N8") (pinfunction "DAT4_N8") (pintype "passive+no_connect"))
    )
    (net (code "79") (name "unconnected-(U6A-DAT5-PadK8)") (class "Default")
      (node (ref "U6") (pin "K8") (pinfunction "DAT5_K8") (pintype "passive+no_connect"))
    )
    (net (code "80") (name "unconnected-(U6A-DAT6-PadN9)") (class "Default")
      (node (ref "U6") (pin "N9") (pinfunction "DAT6_N9") (pintype "passive+no_connect"))
    )
    (net (code "81") (name "unconnected-(U6A-DAT7-PadK9)") (class "Default")
      (node (ref "U6") (pin "K9") (pinfunction "DAT7_K9") (pintype "passive+no_connect"))
    )
    (net (code "82") (name "unconnected-(U6A-DS-PadK5)") (class "Default")
      (node (ref "U6") (pin "K5") (pinfunction "DS_K5") (pintype "passive+no_connect"))
    )
    (net (code "83") (name "unconnected-(U6A-VSF1-PadD2)") (class "Default")
      (node (ref "U6") (pin "D2") (pinfunction "VSF1_D2") (pintype "passive+no_connect"))
    )
    (net (code "84") (name "unconnected-(U6A-VSF2-PadD3)") (class "Default")
      (node (ref "U6") (pin "D3") (pinfunction "VSF2_D3") (pintype "passive+no_connect"))
    )
    (net (code "85") (name "unconnected-(U6A-VSF3-PadD4)") (class "Default")
      (node (ref "U6") (pin "D4") (pinfunction "VSF3_D4") (pintype "passive+no_connect"))
    )
    (net (code "86") (name "unconnected-(U6A-VSF4-PadD5)") (class "Default")
      (node (ref "U6") (pin "D5") (pinfunction "VSF4_D5") (pintype "passive+no_connect"))
    )
    (net (code "87") (name "unconnected-(U6A-VSF5-PadD6)") (class "Default")
      (node (ref "U6") (pin "D6") (pinfunction "VSF5_D6") (pintype "passive+no_connect"))
    )
    (net (code "88") (name "unconnected-(U6A-VSF6-PadD7)") (class "Default")
      (node (ref "U6") (pin "D7") (pinfunction "VSF6_D7") (pintype "passive+no_connect"))
    )
    (net (code "89") (name "unconnected-(U6A-VSF7-PadD8)") (class "Default")
      (node (ref "U6") (pin "D8") (pinfunction "VSF7_D8") (pintype "passive+no_connect"))
    )
    (net (code "90") (name "unconnected-(U6A-VSF8-PadD9)") (class "Default")
      (node (ref "U6") (pin "D9") (pinfunction "VSF8_D9") (pintype "passive+no_connect"))
    )
    (net (code "91") (name "unconnected-(U6B-NC-PadA1)") (class "Default")
      (node (ref "U6") (pin "A1") (pinfunction "NC_A1") (pintype "passive+no_connect"))
    )
    (net (code "92") (name "unconnected-(U6B-NC-PadA2)") (class "Default")
      (node (ref "U6") (pin "A2") (pinfunction "NC_A2") (pintype "passive+no_connect"))
    )
    (net (code "93") (name "unconnected-(U6B-NC-PadA9)") (class "Default")
      (node (ref "U6") (pin "A9") (pinfunction "NC_A9") (pintype "passive+no_connect"))
    )
    (net (code "94") (name "unconnected-(U6B-NC-PadA10)") (class "Default")
      (node (ref "U6") (pin "A10") (pinfunction "NC_A10") (pintype "passive+no_connect"))
    )
    (net (code "95") (name "unconnected-(U6B-NC-PadB1)") (class "Default")
      (node (ref "U6") (pin "B1") (pinfunction "NC_B1") (pintype "passive+no_connect"))
    )
    (net (code "96") (name "unconnected-(U6B-NC-PadB10)") (class "Default")
      (node (ref "U6") (pin "B10") (pinfunction "NC_B10") (pintype "passive+no_connect"))
    )
    (net (code "97") (name "unconnected-(U6B-NC-PadT1)") (class "Default")
      (node (ref "U6") (pin "T1") (pinfunction "NC_T1") (pintype "passive+no_connect"))
    )
    (net (code "98") (name "unconnected-(U6B-NC-PadT10)") (class "Default")
      (node (ref "U6") (pin "T10") (pinfunction "NC_T10") (pintype "passive+no_connect"))
    )
    (net (code "99") (name "unconnected-(U6B-NC-PadU1)") (class "Default")
      (node (ref "U6") (pin "U1") (pinfunction "NC_U1") (pintype "passive+no_connect"))
    )
    (net (code "100") (name "unconnected-(U6B-NC-PadU2)") (class "Default")
      (node (ref "U6") (pin "U2") (pinfunction "NC_U2") (pintype "passive+no_connect"))
    )
    (net (code "101") (name "unconnected-(U6B-NC-PadU9)") (class "Default")
      (node (ref "U6") (pin "U9") (pinfunction "NC_U9") (pintype "passive+no_connect"))
    )
    (net (code "102") (name "unconnected-(U6B-NC-PadU10)") (class "Default")
      (node (ref "U6") (pin "U10") (pinfunction "NC_U10") (pintype "passive+no_connect"))
    )
    (net (code "103") (name "unconnected-(U6B-RFU-PadE2)") (class "Default")
      (node (ref "U6") (pin "E2") (pinfunction "RFU_E2") (pintype "passive+no_connect"))
    )
    (net (code "104") (name "unconnected-(U6B-RFU-PadE3)") (class "Default")
      (node (ref "U6") (pin "E3") (pinfunction "RFU_E3") (pintype "passive+no_connect"))
    )
    (net (code "105") (name "unconnected-(U6B-RFU-PadE5)") (class "Default")
      (node (ref "U6") (pin "E5") (pinfunction "RFU_E5") (pintype "passive+no_connect"))
    )
    (net (code "106") (name "unconnected-(U6B-RFU-PadE6)") (class "Default")
      (node (ref "U6") (pin "E6") (pinfunction "RFU_E6") (pintype "passive+no_connect"))
    )
    (net (code "107") (name "unconnected-(U6B-RFU-PadE7)") (class "Default")
      (node (ref "U6") (pin "E7") (pinfunction "RFU_E7") (pintype "passive+no_connect"))
    )
    (net (code "108") (name "unconnected-(U6B-RFU-PadE8)") (class "Default")
      (node (ref "U6") (pin "E8") (pinfunction "RFU_E8") (pintype "passive+no_connect"))
    )
    (net (code "109") (name "unconnected-(U6B-RFU-PadE9)") (class "Default")
      (node (ref "U6") (pin "E9") (pinfunction "RFU_E9") (pintype "passive+no_connect"))
    )
    (net (code "110") (name "unconnected-(U6B-RFU-PadH4)") (class "Default")
      (node (ref "U6") (pin "H4") (pinfunction "RFU_H4") (pintype "passive+no_connect"))
    )
    (net (code "111") (name "unconnected-(U6B-RFU-PadH5)") (class "Default")
      (node (ref "U6") (pin "H5") (pinfunction "RFU_H5") (pintype "passive+no_connect"))
    )
    (net (code "112") (name "unconnected-(U6B-RFU-PadH6)") (class "Default")
      (node (ref "U6") (pin "H6") (pinfunction "RFU_H6") (pintype "passive+no_connect"))
    )
    (net (code "113") (name "unconnected-(U6B-RFU-PadH7)") (class "Default")
      (node (ref "U6") (pin "H7") (pinfunction "RFU_H7") (pintype "passive+no_connect"))
    )
    (net (code "114") (name "unconnected-(U6B-RFU-PadJ2)") (class "Default")
      (node (ref "U6") (pin "J2") (pinfunction "RFU_J2") (pintype "passive+no_connect"))
    )
    (net (code "115") (name "unconnected-(U6B-RFU-PadJ3)") (class "Default")
      (node (ref "U6") (pin "J3") (pinfunction "RFU_J3") (pintype "passive+no_connect"))
    )
    (net (code "116") (name "unconnected-(U6B-RFU-PadJ4)") (class "Default")
      (node (ref "U6") (pin "J4") (pinfunction "RFU_J4") (pintype "passive+no_connect"))
    )
    (net (code "117") (name "unconnected-(U6B-RFU-PadJ6)") (class "Default")
      (node (ref "U6") (pin "J6") (pinfunction "RFU_J6") (pintype "passive+no_connect"))
    )
    (net (code "118") (name "unconnected-(U6B-RFU-PadJ7)") (class "Default")
      (node (ref "U6") (pin "J7") (pinfunction "RFU_J7") (pintype "passive+no_connect"))
    )
    (net (code "119") (name "unconnected-(U6B-RFU-PadJ8)") (class "Default")
      (node (ref "U6") (pin "J8") (pinfunction "RFU_J8") (pintype "passive+no_connect"))
    )
    (net (code "120") (name "unconnected-(U6B-RFU-PadJ9)") (class "Default")
      (node (ref "U6") (pin "J9") (pinfunction "RFU_J9") (pintype "passive+no_connect"))
    )
    (net (code "121") (name "unconnected-(U6B-RFU-PadK4)") (class "Default")
      (node (ref "U6") (pin "K4") (pinfunction "RFU_K4") (pintype "passive+no_connect"))
    )
    (net (code "122") (name "unconnected-(U6B-RFU-PadK6)") (class "Default")
      (node (ref "U6") (pin "K6") (pinfunction "RFU_K6") (pintype "passive+no_connect"))
    )
    (net (code "123") (name "unconnected-(U6B-RFU-PadK7)") (class "Default")
      (node (ref "U6") (pin "K7") (pinfunction "RFU_K7") (pintype "passive+no_connect"))
    )
    (net (code "124") (name "unconnected-(U6B-RFU-PadL5)") (class "Default")
      (node (ref "U6") (pin "L5") (pinfunction "RFU_L5") (pintype "passive+no_connect"))
    )
    (net (code "125") (name "unconnected-(U6B-RFU-PadL6)") (class "Default")
      (node (ref "U6") (pin "L6") (pinfunction "RFU_L6") (pintype "passive+no_connect"))
    )
    (net (code "126") (name "unconnected-(U6B-RFU-PadM2)") (class "Default")
      (node (ref "U6") (pin "M2") (pinfunction "RFU_M2") (pintype "passive+no_connect"))
    )
    (net (code "127") (name "unconnected-(U6B-RFU-PadM3)") (class "Default")
      (node (ref "U6") (pin "M3") (pinfunction "RFU_M3") (pintype "passive+no_connect"))
    )
    (net (code "128") (name "unconnected-(U6B-RFU-PadM6)") (class "Default")
      (node (ref "U6") (pin "M6") (pinfunction "RFU_M6") (pintype "passive+no_connect"))
    )
    (net (code "129") (name "unconnected-(U6B-RFU-PadM8)") (class "Default")
      (node (ref "U6") (pin "M8") (pinfunction "RFU_M8") (pintype "passive+no_connect"))
    )
    (net (code "130") (name "unconnected-(U6B-RFU-PadM9)") (class "Default")
      (node (ref "U6") (pin "M9") (pinfunction "RFU_M9") (pintype "passive+no_connect"))
    )
    (net (code "131") (name "unconnected-(U6B-RFU-PadN4)") (class "Default")
      (node (ref "U6") (pin "N4") (pinfunction "RFU_N4") (pintype "passive+no_connect"))
    )
    (net (code "132") (name "unconnected-(U6B-RFU-PadN5)") (class "Default")
      (node (ref "U6") (pin "N5") (pinfunction "RFU_N5") (pintype "passive+no_connect"))
    )
    (net (code "133") (name "unconnected-(U6B-RFU-PadN6)") (class "Default")
      (node (ref "U6") (pin "N6") (pinfunction "RFU_N6") (pintype "passive+no_connect"))
    )
    (net (code "134") (name "unconnected-(U6B-RFU-PadN7)") (class "Default")
      (node (ref "U6") (pin "N7") (pinfunction "RFU_N7") (pintype "passive+no_connect"))
    )
    (net (code "135") (name "unconnected-(U6B-RFU-PadP4)") (class "Default")
      (node (ref "U6") (pin "P4") (pinfunction "RFU_P4") (pintype "passive+no_connect"))
    )
    (net (code "136") (name "unconnected-(U6B-RFU-PadP7)") (class "Default")
      (node (ref "U6") (pin "P7") (pinfunction "RFU_P7") (pintype "passive+no_connect"))
    )
  )
)
